# PCB_EstAcqua_EAGLE.net
KiCad netlist of a schematic drawn in EAGLE
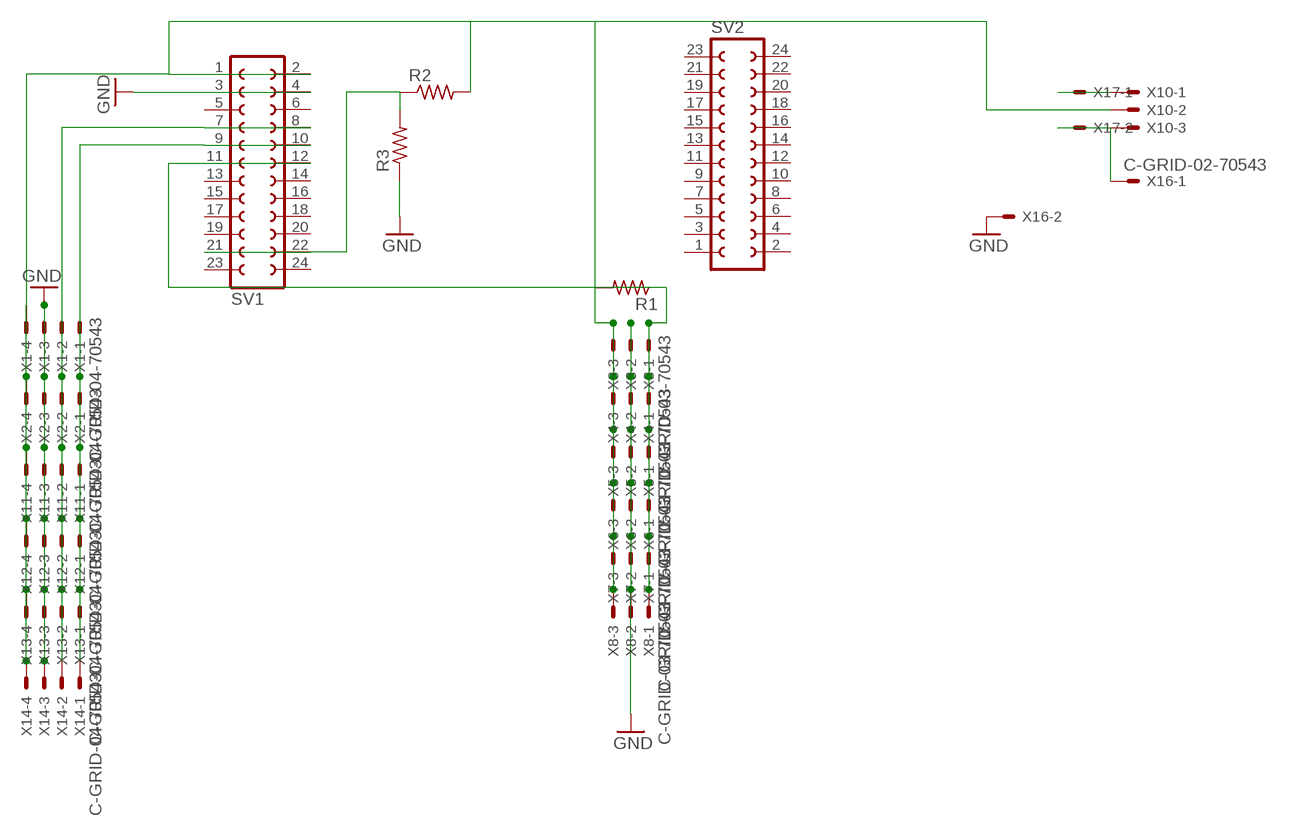
[diagram p0: schematic, sheet 1]

(export (version "E")
  (design (tool "Eeschema 10.0.6"))
  (components
    (comp (ref "R1")
      (value "R-US_0207/15")
      (footprint "eagle-import:0207_15")
      (libsource (lib "eagle-import") (part "resistor_R-US_0207/15"))
    )
    (comp (ref "R2")
      (value "R-US_0207/10")
      (footprint "eagle-import:0207_10")
      (libsource (lib "eagle-import") (part "R-US_0207/10"))
    )
    (comp (ref "R3")
      (value "R-US_0207/10")
      (footprint "eagle-import:0207_10")
      (libsource (lib "eagle-import") (part "R-US_0207/10"))
    )
    (comp (ref "SV1")
      (value "FE12-2W")
      (footprint "eagle-import:FE12-2W")
      (libsource (lib "eagle-import") (part "FE12-2W"))
    )
    (comp (ref "SV2")
      (value "FE12-2W")
      (footprint "eagle-import:FE12-2W")
      (libsource (lib "eagle-import") (part "FE12-2W"))
    )
    (comp (ref "X1")
      (value "C-GRID-04-70543")
      (footprint "eagle-import:70543-04")
      (fields (field (name "MF") "MOLEX"))
      (libsource (lib "eagle-import") (part "C-GRID-04-70543"))
    )
    (comp (ref "X2")
      (value "C-GRID-04-70543")
      (footprint "eagle-import:70543-04")
      (fields (field (name "MF") "MOLEX"))
      (libsource (lib "eagle-import") (part "C-GRID-04-70543"))
    )
    (comp (ref "X3")
      (value "C-GRID-03-70543")
      (footprint "eagle-import:70543-03")
      (fields (field (name "MF") "MOLEX"))
      (libsource (lib "eagle-import") (part "C-GRID-03-70543"))
    )
    (comp (ref "X4")
      (value "C-GRID-03-70543")
      (footprint "eagle-import:70543-03")
      (fields (field (name "MF") "MOLEX"))
      (libsource (lib "eagle-import") (part "C-GRID-03-70543"))
    )
    (comp (ref "X5")
      (value "C-GRID-03-70543")
      (footprint "eagle-import:70543-03")
      (fields (field (name "MF") "MOLEX"))
      (libsource (lib "eagle-import") (part "C-GRID-03-70543"))
    )
    (comp (ref "X6")
      (value "C-GRID-03-70543")
      (footprint "eagle-import:70543-03")
      (fields (field (name "MF") "MOLEX"))
      (libsource (lib "eagle-import") (part "C-GRID-03-70543"))
    )
    (comp (ref "X7")
      (value "C-GRID-03-70543")
      (footprint "eagle-import:70543-03")
      (fields (field (name "MF") "MOLEX"))
      (libsource (lib "eagle-import") (part "C-GRID-03-70543"))
    )
    (comp (ref "X8")
      (value "C-GRID-03-70543")
      (footprint "eagle-import:70543-03")
      (fields (field (name "MF") "MOLEX"))
      (libsource (lib "eagle-import") (part "C-GRID-03-70543"))
    )
    (comp (ref "X10")
      (value "KK-156-3")
      (footprint "eagle-import:KK-156-3")
      (fields (field (name "MF") "MOLEX"))
      (libsource (lib "eagle-import") (part "KK-156-3"))
    )
    (comp (ref "X11")
      (value "C-GRID-04-70543")
      (footprint "eagle-import:70543-04")
      (fields (field (name "MF") "MOLEX"))
      (libsource (lib "eagle-import") (part "C-GRID-04-70543"))
    )
    (comp (ref "X12")
      (value "C-GRID-04-70543")
      (footprint "eagle-import:70543-04")
      (fields (field (name "MF") "MOLEX"))
      (libsource (lib "eagle-import") (part "C-GRID-04-70543"))
    )
    (comp (ref "X13")
      (value "C-GRID-04-70543")
      (footprint "eagle-import:70543-04")
      (fields (field (name "MF") "MOLEX"))
      (libsource (lib "eagle-import") (part "C-GRID-04-70543"))
    )
    (comp (ref "X14")
      (value "C-GRID-04-70543")
      (footprint "eagle-import:70543-04")
      (fields (field (name "MF") "MOLEX"))
      (libsource (lib "eagle-import") (part "C-GRID-04-70543"))
    )
    (comp (ref "X16")
      (value "C-GRID-02-70543")
      (footprint "eagle-import:70543-02")
      (fields (field (name "MF") "MOLEX"))
      (libsource (lib "eagle-import") (part "C-GRID-02-70543"))
    )
    (comp (ref "X17")
      (value "KK-156-2")
      (footprint "eagle-import:KK-156-2")
      (fields (field (name "MF") "MOLEX"))
      (libsource (lib "eagle-import") (part "KK-156-2"))
    )
  )
  (nets
    (net (code "1") (name "GND") (class "Default")
      (node (ref "R3") (pin "1") (pinfunction "1_1") (pintype "passive"))
      (node (ref "SV1") (pin "3") (pinfunction "3_3") (pintype "passive"))
      (node (ref "SV1") (pin "4") (pinfunction "4_4") (pintype "passive"))
      (node (ref "X1") (pin "3") (pinfunction "S_3") (pintype "passive"))
      (node (ref "X11") (pin "3") (pinfunction "S_3") (pintype "passive"))
      (node (ref "X12") (pin "3") (pinfunction "S_3") (pintype "passive"))
      (node (ref "X13") (pin "3") (pinfunction "S_3") (pintype "passive"))
      (node (ref "X14") (pin "3") (pinfunction "S_3") (pintype "passive"))
      (node (ref "X16") (pin "2") (pinfunction "S_2") (pintype "passive"))
      (node (ref "X2") (pin "3") (pinfunction "S_3") (pintype "passive"))
      (node (ref "X3") (pin "2") (pinfunction "S_2") (pintype "passive"))
      (node (ref "X4") (pin "2") (pinfunction "S_2") (pintype "passive"))
      (node (ref "X5") (pin "2") (pinfunction "S_2") (pintype "passive"))
      (node (ref "X6") (pin "2") (pinfunction "S_2") (pintype "passive"))
      (node (ref "X7") (pin "2") (pinfunction "S_2") (pintype "passive"))
      (node (ref "X8") (pin "2") (pinfunction "S_2") (pintype "passive"))
    )
    (net (code "2") (name "Net-(R2-Pad1)") (class "Default")
      (node (ref "R2") (pin "1") (pinfunction "1_1") (pintype "passive"))
      (node (ref "R3") (pin "2") (pinfunction "2_2") (pintype "passive"))
      (node (ref "SV1") (pin "21") (pinfunction "21_21") (pintype "passive"))
      (node (ref "SV1") (pin "22") (pinfunction "22_22") (pintype "passive"))
    )
    (net (code "3") (name "Net-(X3A-S)") (class "Default")
      (node (ref "R1") (pin "1") (pinfunction "1_1") (pintype "passive"))
      (node (ref "SV1") (pin "11") (pinfunction "11_11") (pintype "passive"))
      (node (ref "SV1") (pin "12") (pinfunction "12_12") (pintype "passive"))
      (node (ref "X3") (pin "1") (pinfunction "S_1") (pintype "passive"))
      (node (ref "X4") (pin "1") (pinfunction "S_1") (pintype "passive"))
      (node (ref "X5") (pin "1") (pinfunction "S_1") (pintype "passive"))
      (node (ref "X6") (pin "1") (pinfunction "S_1") (pintype "passive"))
      (node (ref "X7") (pin "1") (pinfunction "S_1") (pintype "passive"))
      (node (ref "X8") (pin "1") (pinfunction "S_1") (pintype "passive"))
    )
    (net (code "4") (name "Net-(X10A-S)") (class "Default")
      (node (ref "X10") (pin "1") (pinfunction "S_1") (pintype "passive"))
      (node (ref "X17") (pin "1") (pinfunction "S_1") (pintype "passive"))
    )
    (net (code "5") (name "Net-(X10B-S)") (class "Default")
      (node (ref "R1") (pin "2") (pinfunction "2_2") (pintype "passive"))
      (node (ref "R2") (pin "2") (pinfunction "2_2") (pintype "passive"))
      (node (ref "SV1") (pin "1") (pinfunction "1_1") (pintype "passive"))
      (node (ref "SV1") (pin "2") (pinfunction "2_2") (pintype "passive"))
      (node (ref "X1") (pin "4") (pinfunction "S_4") (pintype "passive"))
      (node (ref "X10") (pin "2") (pinfunction "S_2") (pintype "passive"))
      (node (ref "X11") (pin "4") (pinfunction "S_4") (pintype "passive"))
      (node (ref "X12") (pin "4") (pinfunction "S_4") (pintype "passive"))
      (node (ref "X13") (pin "4") (pinfunction "S_4") (pintype "passive"))
      (node (ref "X14") (pin "4") (pinfunction "S_4") (pintype "passive"))
      (node (ref "X2") (pin "4") (pinfunction "S_4") (pintype "passive"))
      (node (ref "X3") (pin "3") (pinfunction "S_3") (pintype "passive"))
      (node (ref "X4") (pin "3") (pinfunction "S_3") (pintype "passive"))
      (node (ref "X5") (pin "3") (pinfunction "S_3") (pintype "passive"))
      (node (ref "X6") (pin "3") (pinfunction "S_3") (pintype "passive"))
      (node (ref "X7") (pin "3") (pinfunction "S_3") (pintype "passive"))
      (node (ref "X8") (pin "3") (pinfunction "S_3") (pintype "passive"))
    )
    (net (code "6") (name "Net-(X10C-S)") (class "Default")
      (node (ref "X10") (pin "3") (pinfunction "S_3") (pintype "passive"))
      (node (ref "X16") (pin "1") (pinfunction "S_1") (pintype "passive"))
      (node (ref "X17") (pin "2") (pinfunction "S_2") (pintype "passive"))
    )
    (net (code "7") (name "Net-(X11A-S)") (class "Default")
      (node (ref "SV1") (pin "10") (pinfunction "10_10") (pintype "passive"))
      (node (ref "SV1") (pin "9") (pinfunction "9_9") (pintype "passive"))
      (node (ref "X1") (pin "1") (pinfunction "S_1") (pintype "passive"))
      (node (ref "X11") (pin "1") (pinfunction "S_1") (pintype "passive"))
      (node (ref "X12") (pin "1") (pinfunction "S_1") (pintype "passive"))
      (node (ref "X13") (pin "1") (pinfunction "S_1") (pintype "passive"))
      (node (ref "X14") (pin "1") (pinfunction "S_1") (pintype "passive"))
      (node (ref "X2") (pin "1") (pinfunction "S_1") (pintype "passive"))
    )
    (net (code "8") (name "Net-(X11B-S)") (class "Default")
      (node (ref "SV1") (pin "7") (pinfunction "7_7") (pintype "passive"))
      (node (ref "SV1") (pin "8") (pinfunction "8_8") (pintype "passive"))
      (node (ref "X1") (pin "2") (pinfunction "S_2") (pintype "passive"))
      (node (ref "X11") (pin "2") (pinfunction "S_2") (pintype "passive"))
      (node (ref "X12") (pin "2") (pinfunction "S_2") (pintype "passive"))
      (node (ref "X13") (pin "2") (pinfunction "S_2") (pintype "passive"))
      (node (ref "X14") (pin "2") (pinfunction "S_2") (pintype "passive"))
      (node (ref "X2") (pin "2") (pinfunction "S_2") (pintype "passive"))
    )
    (net (code "9") (name "unconnected-(SV1-Pad5)") (class "Default")
      (node (ref "SV1") (pin "5") (pinfunction "5_5") (pintype "passive"))
    )
    (net (code "10") (name "unconnected-(SV1-Pad6)") (class "Default")
      (node (ref "SV1") (pin "6") (pinfunction "6_6") (pintype "passive"))
    )
    (net (code "11") (name "unconnected-(SV1-Pad13)") (class "Default")
      (node (ref "SV1") (pin "13") (pinfunction "13_13") (pintype "passive"))
    )
    (net (code "12") (name "unconnected-(SV1-Pad14)") (class "Default")
      (node (ref "SV1") (pin "14") (pinfunction "14_14") (pintype "passive"))
    )
    (net (code "13") (name "unconnected-(SV1-Pad15)") (class "Default")
      (node (ref "SV1") (pin "15") (pinfunction "15_15") (pintype "passive"))
    )
    (net (code "14") (name "unconnected-(SV1-Pad16)") (class "Default")
      (node (ref "SV1") (pin "16") (pinfunction "16_16") (pintype "passive"))
    )
    (net (code "15") (name "unconnected-(SV1-Pad17)") (class "Default")
      (node (ref "SV1") (pin "17") (pinfunction "17_17") (pintype "passive"))
    )
    (net (code "16") (name "unconnected-(SV1-Pad18)") (class "Default")
      (node (ref "SV1") (pin "18") (pinfunction "18_18") (pintype "passive"))
    )
    (net (code "17") (name "unconnected-(SV1-Pad19)") (class "Default")
      (node (ref "SV1") (pin "19") (pinfunction "19_19") (pintype "passive"))
    )
    (net (code "18") (name "unconnected-(SV1-Pad20)") (class "Default")
      (node (ref "SV1") (pin "20") (pinfunction "20_20") (pintype "passive"))
    )
    (net (code "19") (name "unconnected-(SV1-Pad23)") (class "Default")
      (node (ref "SV1") (pin "23") (pinfunction "23_23") (pintype "passive"))
    )
    (net (code "20") (name "unconnected-(SV1-Pad24)") (class "Default")
      (node (ref "SV1") (pin "24") (pinfunction "24_24") (pintype "passive"))
    )
    (net (code "21") (name "unconnected-(SV2-Pad1)") (class "Default")
      (node (ref "SV2") (pin "1") (pinfunction "1_1") (pintype "passive"))
    )
    (net (code "22") (name "unconnected-(SV2-Pad2)") (class "Default")
      (node (ref "SV2") (pin "2") (pinfunction "2_2") (pintype "passive"))
    )
    (net (code "23") (name "unconnected-(SV2-Pad3)") (class "Default")
      (node (ref "SV2") (pin "3") (pinfunction "3_3") (pintype "passive"))
    )
    (net (code "24") (name "unconnected-(SV2-Pad4)") (class "Default")
      (node (ref "SV2") (pin "4") (pinfunction "4_4") (pintype "passive"))
    )
    (net (code "25") (name "unconnected-(SV2-Pad5)") (class "Default")
      (node (ref "SV2") (pin "5") (pinfunction "5_5") (pintype "passive"))
    )
    (net (code "26") (name "unconnected-(SV2-Pad6)") (class "Default")
      (node (ref "SV2") (pin "6") (pinfunction "6_6") (pintype "passive"))
    )
    (net (code "27") (name "unconnected-(SV2-Pad7)") (class "Default")
      (node (ref "SV2") (pin "7") (pinfunction "7_7") (pintype "passive"))
    )
    (net (code "28") (name "unconnected-(SV2-Pad8)") (class "Default")
      (node (ref "SV2") (pin "8") (pinfunction "8_8") (pintype "passive"))
    )
    (net (code "29") (name "unconnected-(SV2-Pad9)") (class "Default")
      (node (ref "SV2") (pin "9") (pinfunction "9_9") (pintype "passive"))
    )
    (net (code "30") (name "unconnected-(SV2-Pad10)") (class "Default")
      (node (ref "SV2") (pin "10") (pinfunction "10_10") (pintype "passive"))
    )
    (net (code "31") (name "unconnected-(SV2-Pad11)") (class "Default")
      (node (ref "SV2") (pin "11") (pinfunction "11_11") (pintype "passive"))
    )
    (net (code "32") (name "unconnected-(SV2-Pad12)") (class "Default")
      (node (ref "SV2") (pin "12") (pinfunction "12_12") (pintype "passive"))
    )
    (net (code "33") (name "unconnected-(SV2-Pad13)") (class "Default")
      (node (ref "SV2") (pin "13") (pinfunction "13_13") (pintype "passive"))
    )
    (net (code "34") (name "unconnected-(SV2-Pad14)") (class "Default")
      (node (ref "SV2") (pin "14") (pinfunction "14_14") (pintype "passive"))
    )
    (net (code "35") (name "unconnected-(SV2-Pad15)") (class "Default")
      (node (ref "SV2") (pin "15") (pinfunction "15_15") (pintype "passive"))
    )
    (net (code "36") (name "unconnected-(SV2-Pad16)") (class "Default")
      (node (ref "SV2") (pin "16") (pinfunction "16_16") (pintype "passive"))
    )
    (net (code "37") (name "unconnected-(SV2-Pad17)") (class "Default")
      (node (ref "SV2") (pin "17") (pinfunction "17_17") (pintype "passive"))
    )
    (net (code "38") (name "unconnected-(SV2-Pad18)") (class "Default")
      (node (ref "SV2") (pin "18") (pinfunction "18_18") (pintype "passive"))
    )
    (net (code "39") (name "unconnected-(SV2-Pad19)") (class "Default")
      (node (ref "SV2") (pin "19") (pinfunction "19_19") (pintype "passive"))
    )
    (net (code "40") (name "unconnected-(SV2-Pad20)") (class "Default")
      (node (ref "SV2") (pin "20") (pinfunction "20_20") (pintype "passive"))
    )
    (net (code "41") (name "unconnected-(SV2-Pad21)") (class "Default")
      (node (ref "SV2") (pin "21") (pinfunction "21_21") (pintype "passive"))
    )
    (net (code "42") (name "unconnected-(SV2-Pad22)") (class "Default")
      (node (ref "SV2") (pin "22") (pinfunction "22_22") (pintype "passive"))
    )
    (net (code "43") (name "unconnected-(SV2-Pad23)") (class "Default")
      (node (ref "SV2") (pin "23") (pinfunction "23_23") (pintype "passive"))
    )
    (net (code "44") (name "unconnected-(SV2-Pad24)") (class "Default")
      (node (ref "SV2") (pin "24") (pinfunction "24_24") (pintype "passive"))
    )
  )
)
